# shemLampsV2.net
KiCad netlist of a schematic drawn in EAGLE
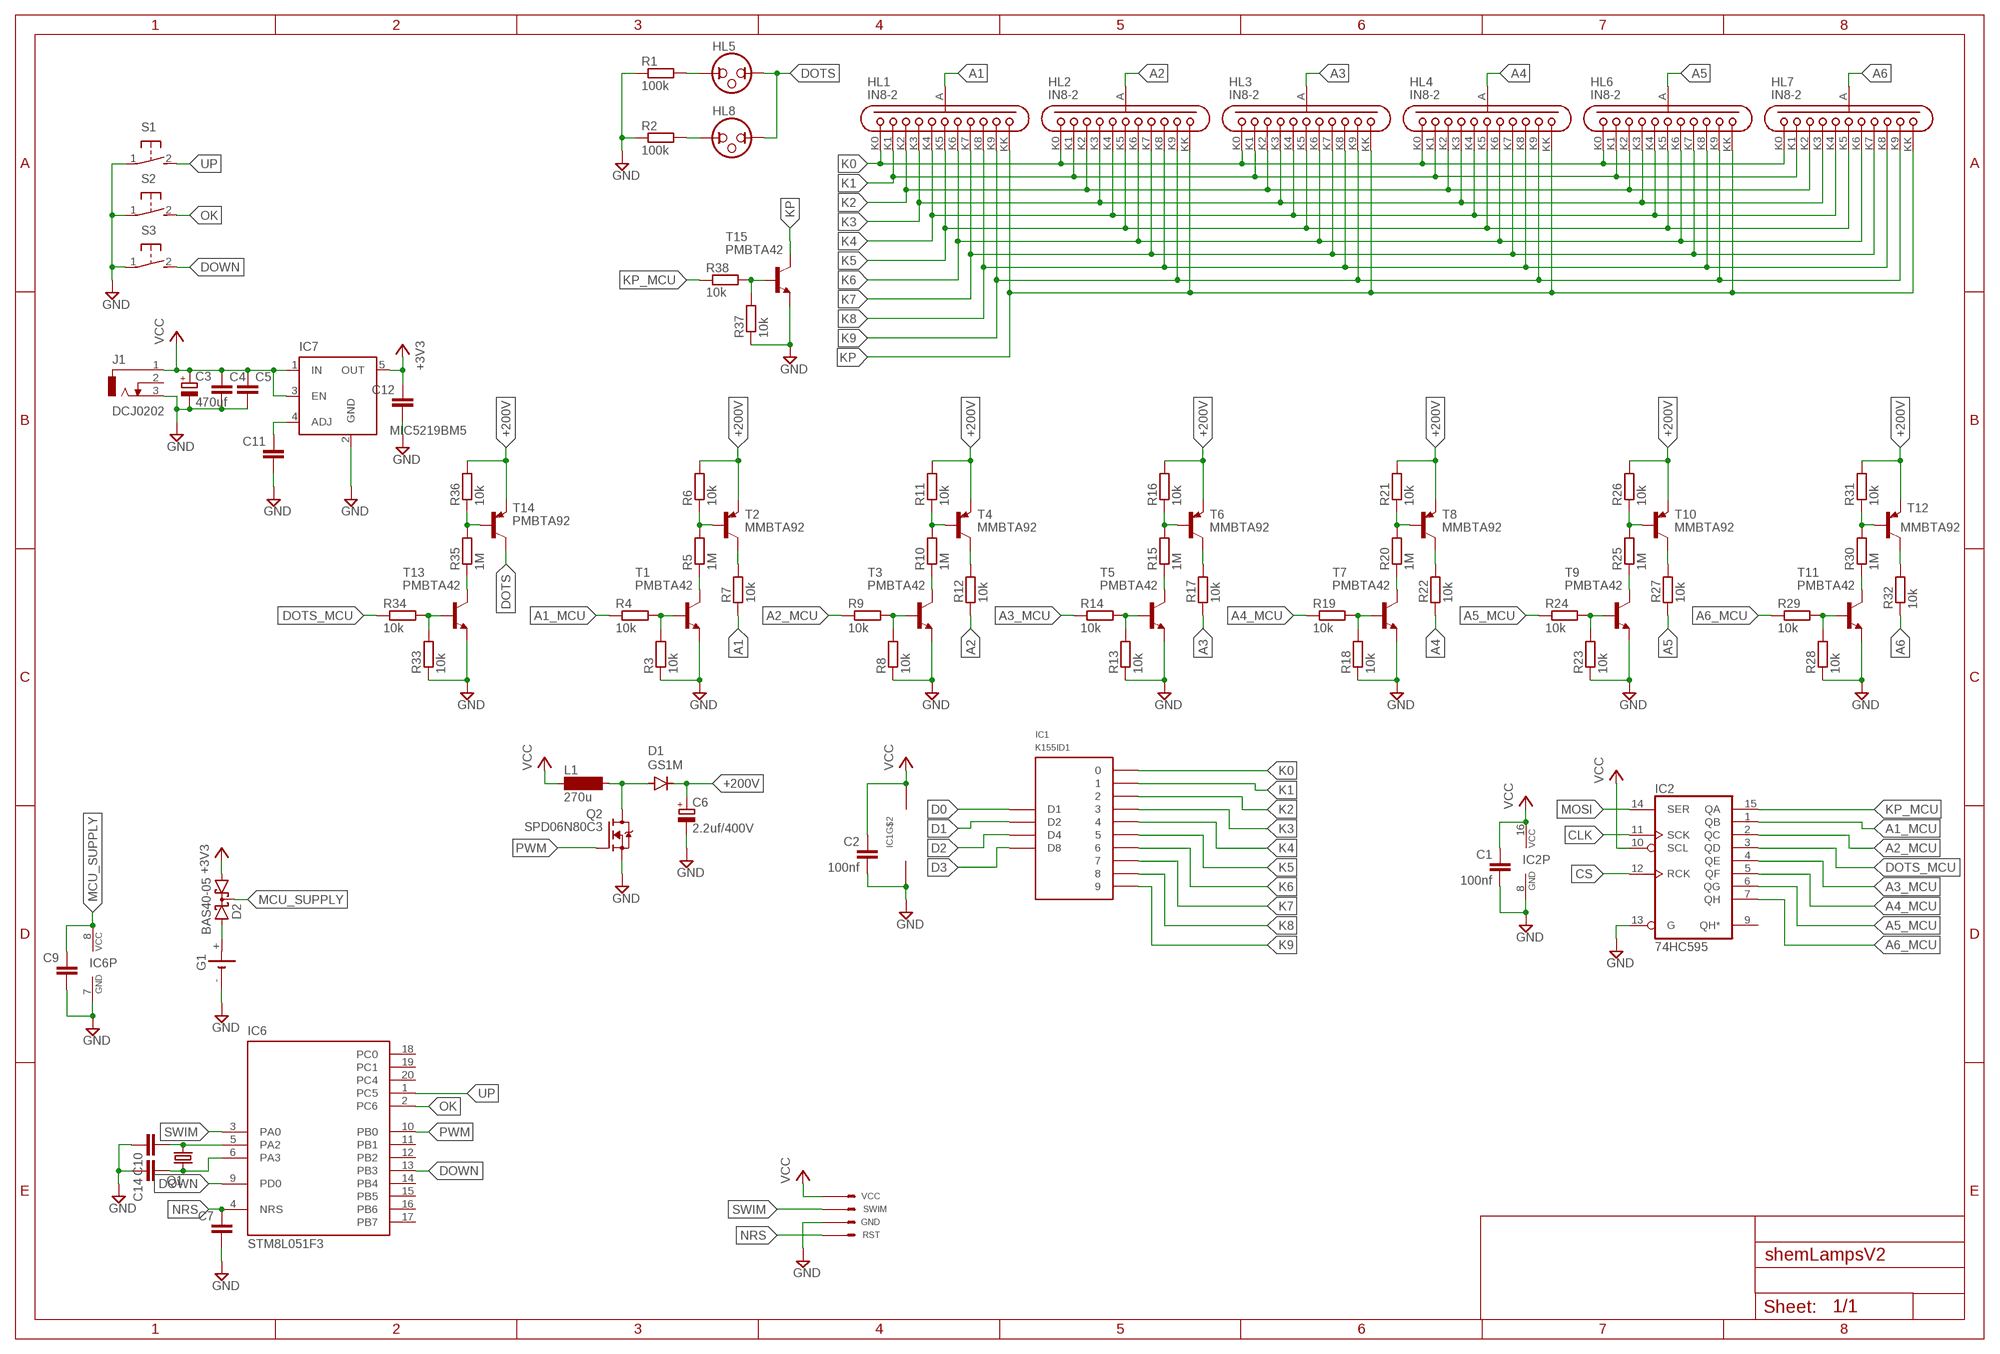
[diagram p0: schematic, sheet 1]

(export (version "E")
  (design (tool "Eeschema 10.0.6"))
  (components
    (comp (ref "C1")
      (value "100nf")
      (footprint "eagle-import:C0805")
      (libsource (lib "eagle-import") (part "CAP"))
    )
    (comp (ref "C2")
      (value "100nf")
      (footprint "eagle-import:C0805")
      (libsource (lib "eagle-import") (part "CAP"))
    )
    (comp (ref "C3")
      (value "470uf")
      (footprint "eagle-import:E3,5-8")
      (libsource (lib "eagle-import") (part "CPOL-EUE3.5-8"))
    )
    (comp (ref "C4")
      (value "C0805")
      (footprint "eagle-import:CAPC2113X70")
      (libsource (lib "eagle-import") (part "C0805"))
    )
    (comp (ref "C5")
      (value "C0805")
      (footprint "eagle-import:CAPC2113X70")
      (libsource (lib "eagle-import") (part "C0805"))
    )
    (comp (ref "C6")
      (value "2.2uf/400V")
      (footprint "eagle-import:E3,5-8")
      (libsource (lib "eagle-import") (part "CPOL-EUE3.5-8"))
    )
    (comp (ref "C7")
      (value "C0805")
      (footprint "eagle-import:CAPC2113X70")
      (libsource (lib "eagle-import") (part "C0805"))
    )
    (comp (ref "C9")
      (value "C0805")
      (footprint "eagle-import:CAPC2113X70")
      (libsource (lib "eagle-import") (part "C0805"))
    )
    (comp (ref "C10")
      (value "C0805")
      (footprint "eagle-import:CAPC2113X70")
      (libsource (lib "eagle-import") (part "C0805"))
    )
    (comp (ref "C11")
      (value "C0805")
      (footprint "eagle-import:CAPC2113X70")
      (libsource (lib "eagle-import") (part "C0805"))
    )
    (comp (ref "C12")
      (value "C0805")
      (footprint "eagle-import:CAPC2113X70")
      (libsource (lib "eagle-import") (part "C0805"))
    )
    (comp (ref "C14")
      (value "C0805")
      (footprint "eagle-import:CAPC2113X70")
      (libsource (lib "eagle-import") (part "C0805"))
    )
    (comp (ref "D1")
      (value "GS1M")
      (footprint "eagle-import:DO-214AC")
      (libsource (lib "eagle-import") (part "DIODE-DO-214AC"))
    )
    (comp (ref "D2")
      (value "BAS40-05")
      (footprint "eagle-import:SOT23")
      (libsource (lib "eagle-import") (part "BAS40-05"))
    )
    (comp (ref "G1")
      (value "BATTERY")
      (footprint "eagle-import:CH291-1220LF_W")
      (libsource (lib "eagle-import") (part "BATTERY"))
    )
    (comp (ref "HL1")
      (value "IN8-2")
      (footprint "eagle-import:IN8-2")
      (libsource (lib "eagle-import") (part "IN8-2"))
    )
    (comp (ref "HL2")
      (value "IN8-2")
      (footprint "eagle-import:IN8-2")
      (libsource (lib "eagle-import") (part "IN8-2"))
    )
    (comp (ref "HL3")
      (value "IN8-2")
      (footprint "eagle-import:IN8-2")
      (libsource (lib "eagle-import") (part "IN8-2"))
    )
    (comp (ref "HL4")
      (value "IN8-2")
      (footprint "eagle-import:IN8-2")
      (libsource (lib "eagle-import") (part "IN8-2"))
    )
    (comp (ref "HL5")
      (value "NEON_LAMP")
      (footprint "eagle-import:NEON_LAMP")
      (libsource (lib "eagle-import") (part "NEON_LAMP"))
    )
    (comp (ref "HL6")
      (value "IN8-2")
      (footprint "eagle-import:IN8-2")
      (libsource (lib "eagle-import") (part "IN8-2"))
    )
    (comp (ref "HL7")
      (value "IN8-2")
      (footprint "eagle-import:IN8-2")
      (libsource (lib "eagle-import") (part "IN8-2"))
    )
    (comp (ref "HL8")
      (value "NEON_LAMP")
      (footprint "eagle-import:NEON_LAMP")
      (libsource (lib "eagle-import") (part "NEON_LAMP"))
    )
    (comp (ref "IC1")
      (value "K155ID1")
      (footprint "eagle-import:DIL16")
      (libsource (lib "eagle-import") (part "K155ID1"))
    )
    (comp (ref "IC2")
      (value "74HC595")
      (footprint "eagle-import:TSSOP16L")
      (libsource (lib "eagle-import") (part "74HC595"))
    )
    (comp (ref "IC6")
      (value "STM8L051F3")
      (footprint "eagle-import:TSSOP-20")
      (libsource (lib "eagle-import") (part "STM8L051F3"))
    )
    (comp (ref "IC7")
      (value "MIC5219BM5")
      (footprint "eagle-import:SOT23-5")
      (fields (field (name "MF") "ALTERA CORPORATION") (field (name "MPN") "MIC5219BM5 TR"))
      (libsource (lib "eagle-import") (part "MIC5219BM5"))
    )
    (comp (ref "J1")
      (value "DCJ0202")
      (footprint "eagle-import:DCJ0202")
      (libsource (lib "eagle-import") (part "DCJ0202"))
    )
    (comp (ref "L1")
      (value "270u")
      (footprint "eagle-import:BS11")
      (libsource (lib "eagle-import") (part "BS11"))
    )
    (comp (ref "Q1")
      (value "FC-12M")
      (footprint "eagle-import:FC-12M")
      (libsource (lib "eagle-import") (part "FC-12M"))
    )
    (comp (ref "Q2")
      (value "SPD06N80C3")
      (footprint "eagle-import:TO252")
      (libsource (lib "eagle-import") (part "SPD06N80C3"))
    )
    (comp (ref "R1")
      (value "100k")
      (footprint "eagle-import:0207_10")
      (libsource (lib "eagle-import") (part "R-EU_0207/10"))
    )
    (comp (ref "R2")
      (value "100k")
      (footprint "eagle-import:0207_10")
      (libsource (lib "eagle-import") (part "R-EU_0207/10"))
    )
    (comp (ref "R3")
      (value "10k")
      (footprint "eagle-import:R0805")
      (libsource (lib "eagle-import") (part "RES"))
    )
    (comp (ref "R4")
      (value "10k")
      (footprint "eagle-import:R0805")
      (libsource (lib "eagle-import") (part "RES"))
    )
    (comp (ref "R5")
      (value "1M")
      (footprint "eagle-import:R0805")
      (libsource (lib "eagle-import") (part "RES"))
    )
    (comp (ref "R6")
      (value "10k")
      (footprint "eagle-import:R0805")
      (libsource (lib "eagle-import") (part "RES"))
    )
    (comp (ref "R7")
      (value "10k")
      (footprint "eagle-import:R0805")
      (libsource (lib "eagle-import") (part "RES"))
    )
    (comp (ref "R8")
      (value "10k")
      (footprint "eagle-import:R0805")
      (libsource (lib "eagle-import") (part "RES"))
    )
    (comp (ref "R9")
      (value "10k")
      (footprint "eagle-import:R0805")
      (libsource (lib "eagle-import") (part "RES"))
    )
    (comp (ref "R10")
      (value "1M")
      (footprint "eagle-import:R0805")
      (libsource (lib "eagle-import") (part "RES"))
    )
    (comp (ref "R11")
      (value "10k")
      (footprint "eagle-import:R0805")
      (libsource (lib "eagle-import") (part "RES"))
    )
    (comp (ref "R12")
      (value "10k")
      (footprint "eagle-import:R0805")
      (libsource (lib "eagle-import") (part "RES"))
    )
    (comp (ref "R13")
      (value "10k")
      (footprint "eagle-import:R0805")
      (libsource (lib "eagle-import") (part "RES"))
    )
    (comp (ref "R14")
      (value "10k")
      (footprint "eagle-import:R0805")
      (libsource (lib "eagle-import") (part "RES"))
    )
    (comp (ref "R15")
      (value "1M")
      (footprint "eagle-import:R0805")
      (libsource (lib "eagle-import") (part "RES"))
    )
    (comp (ref "R16")
      (value "10k")
      (footprint "eagle-import:R0805")
      (libsource (lib "eagle-import") (part "RES"))
    )
    (comp (ref "R17")
      (value "10k")
      (footprint "eagle-import:R0805")
      (libsource (lib "eagle-import") (part "RES"))
    )
    (comp (ref "R18")
      (value "10k")
      (footprint "eagle-import:R0805")
      (libsource (lib "eagle-import") (part "RES"))
    )
    (comp (ref "R19")
      (value "10k")
      (footprint "eagle-import:R0805")
      (libsource (lib "eagle-import") (part "RES"))
    )
    (comp (ref "R20")
      (value "1M")
      (footprint "eagle-import:R0805")
      (libsource (lib "eagle-import") (part "RES"))
    )
    (comp (ref "R21")
      (value "10k")
      (footprint "eagle-import:R0805")
      (libsource (lib "eagle-import") (part "RES"))
    )
    (comp (ref "R22")
      (value "10k")
      (footprint "eagle-import:R0805")
      (libsource (lib "eagle-import") (part "RES"))
    )
    (comp (ref "R23")
      (value "10k")
      (footprint "eagle-import:R0805")
      (libsource (lib "eagle-import") (part "RES"))
    )
    (comp (ref "R24")
      (value "10k")
      (footprint "eagle-import:R0805")
      (libsource (lib "eagle-import") (part "RES"))
    )
    (comp (ref "R25")
      (value "1M")
      (footprint "eagle-import:R0805")
      (libsource (lib "eagle-import") (part "RES"))
    )
    (comp (ref "R26")
      (value "10k")
      (footprint "eagle-import:R0805")
      (libsource (lib "eagle-import") (part "RES"))
    )
    (comp (ref "R27")
      (value "10k")
      (footprint "eagle-import:R0805")
      (libsource (lib "eagle-import") (part "RES"))
    )
    (comp (ref "R28")
      (value "10k")
      (footprint "eagle-import:R0805")
      (libsource (lib "eagle-import") (part "RES"))
    )
    (comp (ref "R29")
      (value "10k")
      (footprint "eagle-import:R0805")
      (libsource (lib "eagle-import") (part "RES"))
    )
    (comp (ref "R30")
      (value "1M")
      (footprint "eagle-import:R0805")
      (libsource (lib "eagle-import") (part "RES"))
    )
    (comp (ref "R31")
      (value "10k")
      (footprint "eagle-import:R0805")
      (libsource (lib "eagle-import") (part "RES"))
    )
    (comp (ref "R32")
      (value "10k")
      (footprint "eagle-import:R0805")
      (libsource (lib "eagle-import") (part "RES"))
    )
    (comp (ref "R33")
      (value "10k")
      (footprint "eagle-import:R0805")
      (libsource (lib "eagle-import") (part "RES"))
    )
    (comp (ref "R34")
      (value "10k")
      (footprint "eagle-import:R0805")
      (libsource (lib "eagle-import") (part "RES"))
    )
    (comp (ref "R35")
      (value "1M")
      (footprint "eagle-import:R0805")
      (libsource (lib "eagle-import") (part "RES"))
    )
    (comp (ref "R36")
      (value "10k")
      (footprint "eagle-import:R0805")
      (libsource (lib "eagle-import") (part "RES"))
    )
    (comp (ref "R37")
      (value "10k")
      (footprint "eagle-import:R0805")
      (libsource (lib "eagle-import") (part "RES"))
    )
    (comp (ref "R38")
      (value "10k")
      (footprint "eagle-import:R0805")
      (libsource (lib "eagle-import") (part "RES"))
    )
    (comp (ref "S1")
      (value "31-XX")
      (footprint "eagle-import:B3F-31XX")
      (fields (field (name "MPN") "B3F-3100"))
      (libsource (lib "eagle-import") (part "31-XX"))
    )
    (comp (ref "S2")
      (value "31-XX")
      (footprint "eagle-import:B3F-31XX")
      (fields (field (name "MPN") "B3F-3100"))
      (libsource (lib "eagle-import") (part "31-XX"))
    )
    (comp (ref "S3")
      (value "31-XX")
      (footprint "eagle-import:B3F-31XX")
      (fields (field (name "MPN") "B3F-3100"))
      (libsource (lib "eagle-import") (part "31-XX"))
    )
    (comp (ref "SV1")
      (value "SWIM")
      (footprint "eagle-import:SWIM")
      (libsource (lib "eagle-import") (part "SWIM"))
    )
    (comp (ref "T1")
      (value "PMBTA42")
      (footprint "eagle-import:SOT23-BEC")
      (libsource (lib "eagle-import") (part "-NPN-SOT23-BECBC817-16"))
    )
    (comp (ref "T2")
      (value "MMBTA92")
      (footprint "eagle-import:SOT23-BEC")
      (libsource (lib "eagle-import") (part "-PNP-SOT23-BECBC807-16"))
    )
    (comp (ref "T3")
      (value "PMBTA42")
      (footprint "eagle-import:SOT23-BEC")
      (libsource (lib "eagle-import") (part "-NPN-SOT23-BECBC817-16"))
    )
    (comp (ref "T4")
      (value "MMBTA92")
      (footprint "eagle-import:SOT23-BEC")
      (libsource (lib "eagle-import") (part "-PNP-SOT23-BECBC807-16"))
    )
    (comp (ref "T5")
      (value "PMBTA42")
      (footprint "eagle-import:SOT23-BEC")
      (libsource (lib "eagle-import") (part "-NPN-SOT23-BECBC817-16"))
    )
    (comp (ref "T6")
      (value "MMBTA92")
      (footprint "eagle-import:SOT23-BEC")
      (libsource (lib "eagle-import") (part "-PNP-SOT23-BECBC807-16"))
    )
    (comp (ref "T7")
      (value "PMBTA42")
      (footprint "eagle-import:SOT23-BEC")
      (libsource (lib "eagle-import") (part "-NPN-SOT23-BECBC817-16"))
    )
    (comp (ref "T8")
      (value "MMBTA92")
      (footprint "eagle-import:SOT23-BEC")
      (libsource (lib "eagle-import") (part "-PNP-SOT23-BECBC807-16"))
    )
    (comp (ref "T9")
      (value "PMBTA42")
      (footprint "eagle-import:SOT23-BEC")
      (libsource (lib "eagle-import") (part "-NPN-SOT23-BECBC817-16"))
    )
    (comp (ref "T10")
      (value "MMBTA92")
      (footprint "eagle-import:SOT23-BEC")
      (libsource (lib "eagle-import") (part "-PNP-SOT23-BECBC807-16"))
    )
    (comp (ref "T11")
      (value "PMBTA42")
      (footprint "eagle-import:SOT23-BEC")
      (libsource (lib "eagle-import") (part "-NPN-SOT23-BECBC817-16"))
    )
    (comp (ref "T12")
      (value "MMBTA92")
      (footprint "eagle-import:SOT23-BEC")
      (libsource (lib "eagle-import") (part "-PNP-SOT23-BECBC807-16"))
    )
    (comp (ref "T13")
      (value "PMBTA42")
      (footprint "eagle-import:SOT23-BEC")
      (libsource (lib "eagle-import") (part "-NPN-SOT23-BECBC817-16"))
    )
    (comp (ref "T14")
      (value "PMBTA92")
      (footprint "eagle-import:SOT23-BEC")
      (libsource (lib "eagle-import") (part "-PNP-SOT23-BECBC807-16"))
    )
    (comp (ref "T15")
      (value "PMBTA42")
      (footprint "eagle-import:SOT23-BEC")
      (libsource (lib "eagle-import") (part "-NPN-SOT23-BECBC817-16"))
    )
  )
  (nets
    (net (code "1") (name "+3V3") (class "Default")
      (node (ref "C12") (pin "1") (pinfunction "1_1") (pintype "passive"))
      (node (ref "D2") (pin "1") (pinfunction "A1_1") (pintype "passive"))
      (node (ref "IC7") (pin "5") (pinfunction "OUT_5") (pintype "output"))
    )
    (net (code "2") (name "+200V") (class "Default")
      (node (ref "C6") (pin "+") (pinfunction "+_+") (pintype "passive"))
      (node (ref "D1") (pin "C") (pinfunction "C_C") (pintype "passive"))
      (node (ref "R11") (pin "2") (pinfunction "2_2") (pintype "passive"))
      (node (ref "R16") (pin "2") (pinfunction "2_2") (pintype "passive"))
      (node (ref "R21") (pin "2") (pinfunction "2_2") (pintype "passive"))
      (node (ref "R26") (pin "2") (pinfunction "2_2") (pintype "passive"))
      (node (ref "R31") (pin "2") (pinfunction "2_2") (pintype "passive"))
      (node (ref "R36") (pin "2") (pinfunction "2_2") (pintype "passive"))
      (node (ref "R6") (pin "2") (pinfunction "2_2") (pintype "passive"))
      (node (ref "T10") (pin "E") (pinfunction "E_E") (pintype "passive"))
      (node (ref "T12") (pin "E") (pinfunction "E_E") (pintype "passive"))
      (node (ref "T14") (pin "E") (pinfunction "E_E") (pintype "passive"))
      (node (ref "T2") (pin "E") (pinfunction "E_E") (pintype "passive"))
      (node (ref "T4") (pin "E") (pinfunction "E_E") (pintype "passive"))
      (node (ref "T6") (pin "E") (pinfunction "E_E") (pintype "passive"))
      (node (ref "T8") (pin "E") (pinfunction "E_E") (pintype "passive"))
    )
    (net (code "3") (name "A1") (class "Default")
      (node (ref "HL1") (pin "A") (pinfunction "A_A") (pintype "passive"))
      (node (ref "R7") (pin "1") (pinfunction "1_1") (pintype "passive"))
    )
    (net (code "4") (name "A1_MCU") (class "Default")
      (node (ref "IC2") (pin "1") (pinfunction "QB_1") (pintype "tri_state"))
      (node (ref "R4") (pin "1") (pinfunction "1_1") (pintype "passive"))
    )
    (net (code "5") (name "A2") (class "Default")
      (node (ref "HL2") (pin "A") (pinfunction "A_A") (pintype "passive"))
      (node (ref "R12") (pin "1") (pinfunction "1_1") (pintype "passive"))
    )
    (net (code "6") (name "A2_MCU") (class "Default")
      (node (ref "IC2") (pin "2") (pinfunction "QC_2") (pintype "tri_state"))
      (node (ref "R9") (pin "1") (pinfunction "1_1") (pintype "passive"))
    )
    (net (code "7") (name "A3") (class "Default")
      (node (ref "HL3") (pin "A") (pinfunction "A_A") (pintype "passive"))
      (node (ref "R17") (pin "1") (pinfunction "1_1") (pintype "passive"))
    )
    (net (code "8") (name "A3_MCU") (class "Default")
      (node (ref "IC2") (pin "4") (pinfunction "QE_4") (pintype "tri_state"))
      (node (ref "R14") (pin "1") (pinfunction "1_1") (pintype "passive"))
    )
    (net (code "9") (name "A4") (class "Default")
      (node (ref "HL4") (pin "A") (pinfunction "A_A") (pintype "passive"))
      (node (ref "R22") (pin "1") (pinfunction "1_1") (pintype "passive"))
    )
    (net (code "10") (name "A4_MCU") (class "Default")
      (node (ref "IC2") (pin "5") (pinfunction "QF_5") (pintype "tri_state"))
      (node (ref "R19") (pin "1") (pinfunction "1_1") (pintype "passive"))
    )
    (net (code "11") (name "A5") (class "Default")
      (node (ref "HL6") (pin "A") (pinfunction "A_A") (pintype "passive"))
      (node (ref "R27") (pin "1") (pinfunction "1_1") (pintype "passive"))
    )
    (net (code "12") (name "A5_MCU") (class "Default")
      (node (ref "IC2") (pin "6") (pinfunction "QG_6") (pintype "tri_state"))
      (node (ref "R24") (pin "1") (pinfunction "1_1") (pintype "passive"))
    )
    (net (code "13") (name "A6") (class "Default")
      (node (ref "HL7") (pin "A") (pinfunction "A_A") (pintype "passive"))
      (node (ref "R32") (pin "1") (pinfunction "1_1") (pintype "passive"))
    )
    (net (code "14") (name "A6_MCU") (class "Default")
      (node (ref "IC2") (pin "7") (pinfunction "QH_7") (pintype "tri_state"))
      (node (ref "R29") (pin "1") (pinfunction "1_1") (pintype "passive"))
    )
    (net (code "15") (name "CLK") (class "Default")
      (node (ref "IC2") (pin "11") (pinfunction "SCK_11") (pintype "input"))
    )
    (net (code "16") (name "CS") (class "Default")
      (node (ref "IC2") (pin "12") (pinfunction "RCK_12") (pintype "input"))
    )
    (net (code "17") (name "D0") (class "Default")
      (node (ref "IC1") (pin "3") (pinfunction "D1_3") (pintype "input"))
    )
    (net (code "18") (name "D1") (class "Default")
      (node (ref "IC1") (pin "6") (pinfunction "D2_6") (pintype "input"))
    )
    (net (code "19") (name "D2") (class "Default")
      (node (ref "IC1") (pin "7") (pinfunction "D4_7") (pintype "input"))
    )
    (net (code "20") (name "D3") (class "Default")
      (node (ref "IC1") (pin "4") (pinfunction "D8_4") (pintype "input"))
    )
    (net (code "21") (name "DOTS") (class "Default")
      (node (ref "HL5") (pin "2") (pinfunction "2_2") (pintype "passive"))
      (node (ref "HL8") (pin "2") (pinfunction "2_2") (pintype "passive"))
      (node (ref "T14") (pin "C") (pinfunction "C_C") (pintype "passive"))
    )
    (net (code "22") (name "DOTS_MCU") (class "Default")
      (node (ref "IC2") (pin "3") (pinfunction "QD_3") (pintype "tri_state"))
      (node (ref "R34") (pin "1") (pinfunction "1_1") (pintype "passive"))
    )
    (net (code "23") (name "DOWN") (class "Default")
      (node (ref "IC6") (pin "13") (pinfunction "PB3_13") (pintype "bidirectional"))
      (node (ref "IC6") (pin "9") (pinfunction "PD0_9") (pintype "bidirectional"))
      (node (ref "S3") (pin "2") (pinfunction "S_2") (pintype "passive"))
    )
    (net (code "24") (name "GND") (class "Default")
      (node (ref "C1") (pin "2") (pinfunction "2_2") (pintype "passive"))
      (node (ref "C10") (pin "1") (pinfunction "1_1") (pintype "passive"))
      (node (ref "C11") (pin "2") (pinfunction "2_2") (pintype "passive"))
      (node (ref "C12") (pin "2") (pinfunction "2_2") (pintype "passive"))
      (node (ref "C14") (pin "1") (pinfunction "1_1") (pintype "passive"))
      (node (ref "C2") (pin "2") (pinfunction "2_2") (pintype "passive"))
      (node (ref "C3") (pin "-") (pinfunction "-_-") (pintype "passive"))
      (node (ref "C4") (pin "2") (pinfunction "2_2") (pintype "passive"))
      (node (ref "C5") (pin "2") (pinfunction "2_2") (pintype "passive"))
      (node (ref "C6") (pin "-") (pinfunction "-_-") (pintype "passive"))
      (node (ref "C7") (pin "2") (pinfunction "2_2") (pintype "passive"))
      (node (ref "C9") (pin "2") (pinfunction "2_2") (pintype "passive"))
      (node (ref "G1") (pin "-") (pinfunction "-_-") (pintype "passive"))
      (node (ref "IC1") (pin "12") (pinfunction "GND_12") (pintype "power_in"))
      (node (ref "IC2") (pin "13") (pinfunction "G_13") (pintype "input"))
      (node (ref "IC2") (pin "8") (pinfunction "GND_8") (pintype "power_in"))
      (node (ref "IC6") (pin "7") (pinfunction "GND_7") (pintype "power_in"))
      (node (ref "IC7") (pin "2") (pinfunction "GND_2") (pintype "power_in"))
      (node (ref "J1") (pin "3") (pinfunction "3_3") (pintype "passive"))
      (node (ref "Q2") (pin "2") (pinfunction "S_2") (pintype "passive"))
      (node (ref "R1") (pin "1") (pinfunction "1_1") (pintype "passive"))
      (node (ref "R13") (pin "1") (pinfunction "1_1") (pintype "passive"))
      (node (ref "R18") (pin "1") (pinfunction "1_1") (pintype "passive"))
      (node (ref "R2") (pin "1") (pinfunction "1_1") (pintype "passive"))
      (node (ref "R23") (pin "1") (pinfunction "1_1") (pintype "passive"))
      (node (ref "R28") (pin "1") (pinfunction "1_1") (pintype "passive"))
      (node (ref "R3") (pin "1") (pinfunction "1_1") (pintype "passive"))
      (node (ref "R33") (pin "1") (pinfunction "1_1") (pintype "passive"))
      (node (ref "R37") (pin "1") (pinfunction "1_1") (pintype "passive"))
      (node (ref "R8") (pin "1") (pinfunction "1_1") (pintype "passive"))
      (node (ref "S1") (pin "1") (pinfunction "P_1") (pintype "passive"))
      (node (ref "S2") (pin "1") (pinfunction "P_1") (pintype "passive"))
      (node (ref "S3") (pin "1") (pinfunction "P_1") (pintype "passive"))
      (node (ref "SV1") (pin "GND") (pinfunction "GND_GND") (pintype "power_in"))
      (node (ref "T1") (pin "E") (pinfunction "E_E") (pintype "passive"))
      (node (ref "T11") (pin "E") (pinfunction "E_E") (pintype "passive"))
      (node (ref "T13") (pin "E") (pinfunction "E_E") (pintype "passive"))
      (node (ref "T15") (pin "E") (pinfunction "E_E") (pintype "passive"))
      (node (ref "T3") (pin "E") (pinfunction "E_E") (pintype "passive"))
      (node (ref "T5") (pin "E") (pinfunction "E_E") (pintype "passive"))
      (node (ref "T7") (pin "E") (pinfunction "E_E") (pintype "passive"))
      (node (ref "T9") (pin "E") (pinfunction "E_E") (pintype "passive"))
    )
    (net (code "25") (name "K0") (class "Default")
      (node (ref "HL1") (pin "K0") (pinfunction "K0_K0") (pintype "passive"))
      (node (ref "HL2") (pin "K0") (pinfunction "K0_K0") (pintype "passive"))
      (node (ref "HL3") (pin "K0") (pinfunction "K0_K0") (pintype "passive"))
      (node (ref "HL4") (pin "K0") (pinfunction "K0_K0") (pintype "passive"))
      (node (ref "HL6") (pin "K0") (pinfunction "K0_K0") (pintype "passive"))
      (node (ref "HL7") (pin "K0") (pinfunction "K0_K0") (pintype "passive"))
      (node (ref "IC1") (pin "16") (pinfunction "0_16") (pintype "output"))
    )
    (net (code "26") (name "K1") (class "Default")
      (node (ref "HL1") (pin "K1") (pinfunction "K1_K1") (pintype "passive"))
      (node (ref "HL2") (pin "K1") (pinfunction "K1_K1") (pintype "passive"))
      (node (ref "HL3") (pin "K1") (pinfunction "K1_K1") (pintype "passive"))
      (node (ref "HL4") (pin "K1") (pinfunction "K1_K1") (pintype "passive"))
      (node (ref "HL6") (pin "K1") (pinfunction "K1_K1") (pintype "passive"))
      (node (ref "HL7") (pin "K1") (pinfunction "K1_K1") (pintype "passive"))
      (node (ref "IC1") (pin "15") (pinfunction "1_15") (pintype "output"))
    )
    (net (code "27") (name "K2") (class "Default")
      (node (ref "HL1") (pin "K2") (pinfunction "K2_K2") (pintype "passive"))
      (node (ref "HL2") (pin "K2") (pinfunction "K2_K2") (pintype "passive"))
      (node (ref "HL3") (pin "K2") (pinfunction "K2_K2") (pintype "passive"))
      (node (ref "HL4") (pin "K2") (pinfunction "K2_K2") (pintype "passive"))
      (node (ref "HL6") (pin "K2") (pinfunction "K2_K2") (pintype "passive"))
      (node (ref "HL7") (pin "K2") (pinfunction "K2_K2") (pintype "passive"))
      (node (ref "IC1") (pin "8") (pinfunction "2_8") (pintype "output"))
    )
    (net (code "28") (name "K3") (class "Default")
      (node (ref "HL1") (pin "K3") (pinfunction "K3_K3") (pintype "passive"))
      (node (ref "HL2") (pin "K3") (pinfunction "K3_K3") (pintype "passive"))
      (node (ref "HL3") (pin "K3") (pinfunction "K3_K3") (pintype "passive"))
      (node (ref "HL4") (pin "K3") (pinfunction "K3_K3") (pintype "passive"))
      (node (ref "HL6") (pin "K3") (pinfunction "K3_K3") (pintype "passive"))
      (node (ref "HL7") (pin "K3") (pinfunction "K3_K3") (pintype "passive"))
      (node (ref "IC1") (pin "9") (pinfunction "3_9") (pintype "output"))
    )
    (net (code "29") (name "K4") (class "Default")
      (node (ref "HL1") (pin "K4") (pinfunction "K4_K4") (pintype "passive"))
      (node (ref "HL2") (pin "K4") (pinfunction "K4_K4") (pintype "passive"))
      (node (ref "HL3") (pin "K4") (pinfunction "K4_K4") (pintype "passive"))
      (node (ref "HL4") (pin "K4") (pinfunction "K4_K4") (pintype "passive"))
      (node (ref "HL6") (pin "K4") (pinfunction "K4_K4") (pintype "passive"))
      (node (ref "HL7") (pin "K4") (pinfunction "K4_K4") (pintype "passive"))
      (node (ref "IC1") (pin "13") (pinfunction "4_13") (pintype "output"))
    )
    (net (code "30") (name "K5") (class "Default")
      (node (ref "HL1") (pin "K5") (pinfunction "K5_K5") (pintype "passive"))
      (node (ref "HL2") (pin "K5") (pinfunction "K5_K5") (pintype "passive"))
      (node (ref "HL3") (pin "K5") (pinfunction "K5_K5") (pintype "passive"))
      (node (ref "HL4") (pin "K5") (pinfunction "K5_K5") (pintype "passive"))
      (node (ref "HL6") (pin "K5") (pinfunction "K5_K5") (pintype "passive"))
      (node (ref "HL7") (pin "K5") (pinfunction "K5_K5") (pintype "passive"))
      (node (ref "IC1") (pin "14") (pinfunction "5_14") (pintype "output"))
    )
    (net (code "31") (name "K6") (class "Default")
      (node (ref "HL1") (pin "K6") (pinfunction "K6_K6") (pintype "passive"))
      (node (ref "HL2") (pin "K6") (pinfunction "K6_K6") (pintype "passive"))
      (node (ref "HL3") (pin "K6") (pinfunction "K6_K6") (pintype "passive"))
      (node (ref "HL4") (pin "K6") (pinfunction "K6_K6") (pintype "passive"))
      (node (ref "HL6") (pin "K6") (pinfunction "K6_K6") (pintype "passive"))
      (node (ref "HL7") (pin "K6") (pinfunction "K6_K6") (pintype "passive"))
      (node (ref "IC1") (pin "11") (pinfunction "6_11") (pintype "output"))
    )
    (net (code "32") (name "K7") (class "Default")
      (node (ref "HL1") (pin "K7") (pinfunction "K7_K7") (pintype "passive"))
      (node (ref "HL2") (pin "K7") (pinfunction "K7_K7") (pintype "passive"))
      (node (ref "HL3") (pin "K7") (pinfunction "K7_K7") (pintype "passive"))
      (node (ref "HL4") (pin "K7") (pinfunction "K7_K7") (pintype "passive"))
      (node (ref "HL6") (pin "K7") (pinfunction "K7_K7") (pintype "passive"))
      (node (ref "HL7") (pin "K7") (pinfunction "K7_K7") (pintype "passive"))
      (node (ref "IC1") (pin "10") (pinfunction "7_10") (pintype "output"))
    )
    (net (code "33") (name "K8") (class "Default")
      (node (ref "HL1") (pin "K8") (pinfunction "K8_K8") (pintype "passive"))
      (node (ref "HL2") (pin "K8") (pinfunction "K8_K8") (pintype "passive"))
      (node (ref "HL3") (pin "K8") (pinfunction "K8_K8") (pintype "passive"))
      (node (ref "HL4") (pin "K8") (pinfunction "K8_K8") (pintype "passive"))
      (node (ref "HL6") (pin "K8") (pinfunction "K8_K8") (pintype "passive"))
      (node (ref "HL7") (pin "K8") (pinfunction "K8_K8") (pintype "passive"))
      (node (ref "IC1") (pin "1") (pinfunction "8_1") (pintype "output"))
    )
    (net (code "34") (name "K9") (class "Default")
      (node (ref "HL1") (pin "K9") (pinfunction "K9_K9") (pintype "passive"))
      (node (ref "HL2") (pin "K9") (pinfunction "K9_K9") (pintype "passive"))
      (node (ref "HL3") (pin "K9") (pinfunction "K9_K9") (pintype "passive"))
      (node (ref "HL4") (pin "K9") (pinfunction "K9_K9") (pintype "passive"))
      (node (ref "HL6") (pin "K9") (pinfunction "K9_K9") (pintype "passive"))
      (node (ref "HL7") (pin "K9") (pinfunction "K9_K9") (pintype "passive"))
      (node (ref "IC1") (pin "2") (pinfunction "9_2") (pintype "output"))
    )
    (net (code "35") (name "KP") (class "Default")
      (node (ref "HL1") (pin "KK") (pinfunction "KK_KK") (pintype "passive"))
      (node (ref "HL2") (pin "KK") (pinfunction "KK_KK") (pintype "passive"))
      (node (ref "HL3") (pin "KK") (pinfunction "KK_KK") (pintype "passive"))
      (node (ref "HL4") (pin "KK") (pinfunction "KK_KK") (pintype "passive"))
      (node (ref "HL6") (pin "KK") (pinfunction "KK_KK") (pintype "passive"))
      (node (ref "HL7") (pin "KK") (pinfunction "KK_KK") (pintype "passive"))
      (node (ref "T15") (pin "C") (pinfunction "C_C") (pintype "passive"))
    )
    (net (code "36") (name "KP_MCU") (class "Default")
      (node (ref "IC2") (pin "15") (pinfunction "QA_15") (pintype "tri_state"))
      (node (ref "R38") (pin "1") (pinfunction "1_1") (pintype "passive"))
    )
    (net (code "37") (name "MCU_SUPPLY") (class "Default")
      (node (ref "C9") (pin "1") (pinfunction "1_1") (pintype "passive"))
      (node (ref "D2") (pin "3") (pinfunction "C_3") (pintype "passive"))
      (node (ref "IC6") (pin "8") (pinfunction "VCC_8") (pintype "power_in"))
    )
    (net (code "38") (name "MOSI") (class "Default")
      (node (ref "IC2") (pin "14") (pinfunction "SER_14") (pintype "input"))
    )
    (net (code "39") (name "NRS") (class "Default")
      (node (ref "C7") (pin "1") (pinfunction "1_1") (pintype "passive"))
      (node (ref "IC6") (pin "4") (pinfunction "NRS_4") (pintype "bidirectional"))
      (node (ref "SV1") (pin "NRS") (pinfunction "RST_NRS") (pintype "bidirectional"))
    )
    (net (code "40") (name "Net-(D2-A2)") (class "Default")
      (node (ref "D2") (pin "2") (pinfunction "A2_2") (pintype "passive"))
      (node (ref "G1") (pin "+") (pinfunction "+_+") (pintype "passive"))
    )
    (net (code "41") (name "Net-(HL5-Pad1)") (class "Default")
      (node (ref "HL5") (pin "1") (pinfunction "1_1") (pintype "passive"))
      (node (ref "R1") (pin "2") (pinfunction "2_2") (pintype "passive"))
    )
    (net (code "42") (name "Net-(HL8-Pad1)") (class "Default")
      (node (ref "HL8") (pin "1") (pinfunction "1_1") (pintype "passive"))
      (node (ref "R2") (pin "2") (pinfunction "2_2") (pintype "passive"))
    )
    (net (code "43") (name "Net-(IC6A-PA2)") (class "Default")
      (node (ref "C10") (pin "2") (pinfunction "2_2") (pintype "passive"))
      (node (ref "IC6") (pin "5") (pinfunction "PA2_5") (pintype "bidirectional"))
      (node (ref "Q1") (pin "2") (pinfunction "2_2") (pintype "passive"))
    )
    (net (code "44") (name "Net-(IC6A-PA3)") (class "Default")
      (node (ref "C14") (pin "2") (pinfunction "2_2") (pintype "passive"))
      (node (ref "IC6") (pin "6") (pinfunction "PA3_6") (pintype "bidirectional"))
      (node (ref "Q1") (pin "1") (pinfunction "1_1") (pintype "passive"))
    )
    (net (code "45") (name "Net-(IC7-ADJ)") (class "Default")
      (node (ref "C11") (pin "1") (pinfunction "1_1") (pintype "passive"))
      (node (ref "IC7") (pin "4") (pinfunction "ADJ_4") (pintype "passive"))
    )
    (net (code "46") (name "Net-(Q2-D)") (class "Default")
      (node (ref "D1") (pin "A") (pinfunction "A_A") (pintype "passive"))
      (node (ref "L1") (pin "2") (pinfunction "2_2") (pintype "passive"))
      (node (ref "Q2") (pin "3") (pinfunction "D_3") (pintype "passive"))
    )
    (net (code "47") (name "Net-(R3-Pad2)") (class "Default")
      (node (ref "R3") (pin "2") (pinfunction "2_2") (pintype "passive"))
      (node (ref "R4") (pin "2") (pinfunction "2_2") (pintype "passive"))
      (node (ref "T1") (pin "B") (pinfunction "B_B") (pintype "passive"))
    )
    (net (code "48") (name "Net-(R5-Pad1)") (class "Default")
      (node (ref "R5") (pin "1") (pinfunction "1_1") (pintype "passive"))
      (node (ref "T1") (pin "C") (pinfunction "C_C") (pintype "passive"))
    )
    (net (code "49") (name "Net-(R5-Pad2)") (class "Default")
      (node (ref "R5") (pin "2") (pinfunction "2_2") (pintype "passive"))
      (node (ref "R6") (pin "1") (pinfunction "1_1") (pintype "passive"))
      (node (ref "T2") (pin "B") (pinfunction "B_B") (pintype "passive"))
    )
    (net (code "50") (name "Net-(R7-Pad2)") (class "Default")
      (node (ref "R7") (pin "2") (pinfunction "2_2") (pintype "passive"))
      (node (ref "T2") (pin "C") (pinfunction "C_C") (pintype "passive"))
    )
    (net (code "51") (name "Net-(R8-Pad2)") (class "Default")
      (node (ref "R8") (pin "2") (pinfunction "2_2") (pintype "passive"))
      (node (ref "R9") (pin "2") (pinfunction "2_2") (pintype "passive"))
      (node (ref "T3") (pin "B") (pinfunction "B_B") (pintype "passive"))
    )
    (net (code "52") (name "Net-(R10-Pad1)") (class "Default")
      (node (ref "R10") (pin "1") (pinfunction "1_1") (pintype "passive"))
      (node (ref "T3") (pin "C") (pinfunction "C_C") (pintype "passive"))
    )
    (net (code "53") (name "Net-(R10-Pad2)") (class "Default")
      (node (ref "R10") (pin "2") (pinfunction "2_2") (pintype "passive"))
      (node (ref "R11") (pin "1") (pinfunction "1_1") (pintype "passive"))
      (node (ref "T4") (pin "B") (pinfunction "B_B") (pintype "passive"))
    )
    (net (code "54") (name "Net-(R12-Pad2)") (class "Default")
      (node (ref "R12") (pin "2") (pinfunction "2_2") (pintype "passive"))
      (node (ref "T4") (pin "C") (pinfunction "C_C") (pintype "passive"))
    )
    (net (code "55") (name "Net-(R13-Pad2)") (class "Default")
      (node (ref "R13") (pin "2") (pinfunction "2_2") (pintype "passive"))
      (node (ref "R14") (pin "2") (pinfunction "2_2") (pintype "passive"))
      (node (ref "T5") (pin "B") (pinfunction "B_B") (pintype "passive"))
    )
    (net (code "56") (name "Net-(R15-Pad1)") (class "Default")
      (node (ref "R15") (pin "1") (pinfunction "1_1") (pintype "passive"))
      (node (ref "T5") (pin "C") (pinfunction "C_C") (pintype "passive"))
    )
    (net (code "57") (name "Net-(R15-Pad2)") (class "Default")
      (node (ref "R15") (pin "2") (pinfunction "2_2") (pintype "passive"))
      (node (ref "R16") (pin "1") (pinfunction "1_1") (pintype "passive"))
      (node (ref "T6") (pin "B") (pinfunction "B_B") (pintype "passive"))
    )
    (net (code "58") (name "Net-(R17-Pad2)") (class "Default")
      (node (ref "R17") (pin "2") (pinfunction "2_2") (pintype "passive"))
      (node (ref "T6") (pin "C") (pinfunction "C_C") (pintype "passive"))
    )
    (net (code "59") (name "Net-(R18-Pad2)") (class "Default")
      (node (ref "R18") (pin "2") (pinfunction "2_2") (pintype "passive"))
      (node (ref "R19") (pin "2") (pinfunction "2_2") (pintype "passive"))
      (node (ref "T7") (pin "B") (pinfunction "B_B") (pintype "passive"))
    )
    (net (code "60") (name "Net-(R20-Pad1)") (class "Default")
      (node (ref "R20") (pin "1") (pinfunction "1_1") (pintype "passive"))
      (node (ref "T7") (pin "C") (pinfunction "C_C") (pintype "passive"))
    )
    (net (code "61") (name "Net-(R20-Pad2)") (class "Default")
      (node (ref "R20") (pin "2") (pinfunction "2_2") (pintype "passive"))
      (node (ref "R21") (pin "1") (pinfunction "1_1") (pintype "passive"))
      (node (ref "T8") (pin "B") (pinfunction "B_B") (pintype "passive"))
    )
    (net (code "62") (name "Net-(R22-Pad2)") (class "Default")
      (node (ref "R22") (pin "2") (pinfunction "2_2") (pintype "passive"))
      (node (ref "T8") (pin "C") (pinfunction "C_C") (pintype "passive"))
    )
    (net (code "63") (name "Net-(R23-Pad2)") (class "Default")
      (node (ref "R23") (pin "2") (pinfunction "2_2") (pintype "passive"))
      (node (ref "R24") (pin "2") (pinfunction "2_2") (pintype "passive"))
      (node (ref "T9") (pin "B") (pinfunction "B_B") (pintype "passive"))
    )
    (net (code "64") (name "Net-(R25-Pad1)") (class "Default")
      (node (ref "R25") (pin "1") (pinfunction "1_1") (pintype "passive"))
      (node (ref "T9") (pin "C") (pinfunction "C_C") (pintype "passive"))
    )
    (net (code "65") (name "Net-(R25-Pad2)") (class "Default")
      (node (ref "R25") (pin "2") (pinfunction "2_2") (pintype "passive"))
      (node (ref "R26") (pin "1") (pinfunction "1_1") (pintype "passive"))
      (node (ref "T10") (pin "B") (pinfunction "B_B") (pintype "passive"))
    )
    (net (code "66") (name "Net-(R27-Pad2)") (class "Default")
      (node (ref "R27") (pin "2") (pinfunction "2_2") (pintype "passive"))
      (node (ref "T10") (pin "C") (pinfunction "C_C") (pintype "passive"))
    )
    (net (code "67") (name "Net-(R28-Pad2)") (class "Default")
      (node (ref "R28") (pin "2") (pinfunction "2_2") (pintype "passive"))
      (node (ref "R29") (pin "2") (pinfunction "2_2") (pintype "passive"))
      (node (ref "T11") (pin "B") (pinfunction "B_B") (pintype "passive"))
    )
    (net (code "68") (name "Net-(R30-Pad1)") (class "Default")
      (node (ref "R30") (pin "1") (pinfunction "1_1") (pintype "passive"))
      (node (ref "T11") (pin "C") (pinfunction "C_C") (pintype "passive"))
    )
    (net (code "69") (name "Net-(R30-Pad2)") (class "Default")
      (node (ref "R30") (pin "2") (pinfunction "2_2") (pintype "passive"))
      (node (ref "R31") (pin "1") (pinfunction "1_1") (pintype "passive"))
      (node (ref "T12") (pin "B") (pinfunction "B_B") (pintype "passive"))
    )
    (net (code "70") (name "Net-(R32-Pad2)") (class "Default")
      (node (ref "R32") (pin "2") (pinfunction "2_2") (pintype "passive"))
      (node (ref "T12") (pin "C") (pinfunction "C_C") (pintype "passive"))
    )
    (net (code "71") (name "Net-(R33-Pad2)") (class "Default")
      (node (ref "R33") (pin "2") (pinfunction "2_2") (pintype "passive"))
      (node (ref "R34") (pin "2") (pinfunction "2_2") (pintype "passive"))
      (node (ref "T13") (pin "B") (pinfunction "B_B") (pintype "passive"))
    )
    (net (code "72") (name "Net-(R35-Pad1)") (class "Default")
      (node (ref "R35") (pin "1") (pinfunction "1_1") (pintype "passive"))
      (node (ref "T13") (pin "C") (pinfunction "C_C") (pintype "passive"))
    )
    (net (code "73") (name "Net-(R35-Pad2)") (class "Default")
      (node (ref "R35") (pin "2") (pinfunction "2_2") (pintype "passive"))
      (node (ref "R36") (pin "1") (pinfunction "1_1") (pintype "passive"))
      (node (ref "T14") (pin "B") (pinfunction "B_B") (pintype "passive"))
    )
    (net (code "74") (name "Net-(R37-Pad2)") (class "Default")
      (node (ref "R37") (pin "2") (pinfunction "2_2") (pintype "passive"))
      (node (ref "R38") (pin "2") (pinfunction "2_2") (pintype "passive"))
      (node (ref "T15") (pin "B") (pinfunction "B_B") (pintype "passive"))
    )
    (net (code "75") (name "OK") (class "Default")
      (node (ref "IC6") (pin "2") (pinfunction "PC6_2") (pintype "bidirectional"))
      (node (ref "S2") (pin "2") (pinfunction "S_2") (pintype "passive"))
    )
    (net (code "76") (name "PWM") (class "Default")
      (node (ref "IC6") (pin "10") (pinfunction "PB0_10") (pintype "bidirectional"))
      (node (ref "Q2") (pin "1") (pinfunction "G_1") (pintype "passive"))
    )
    (net (code "77") (name "SWIM") (class "Default")
      (node (ref "IC6") (pin "3") (pinfunction "PA0_3") (pintype "bidirectional"))
      (node (ref "SV1") (pin "SWIM") (pinfunction "SWIM_SWIM") (pintype "bidirectional"))
    )
    (net (code "78") (name "UP") (class "Default")
      (node (ref "IC6") (pin "1") (pinfunction "PC5_1") (pintype "bidirectional"))
      (node (ref "S1") (pin "2") (pinfunction "S_2") (pintype "passive"))
    )
    (net (code "79") (name "VCC") (class "Default")
      (node (ref "C1") (pin "1") (pinfunction "1_1") (pintype "passive"))
      (node (ref "C2") (pin "1") (pinfunction "1_1") (pintype "passive"))
      (node (ref "C3") (pin "+") (pinfunction "+_+") (pintype "passive"))
      (node (ref "C4") (pin "1") (pinfunction "1_1") (pintype "passive"))
      (node (ref "C5") (pin "1") (pinfunction "1_1") (pintype "passive"))
      (node (ref "IC1") (pin "5") (pinfunction "VCC_5") (pintype "power_in"))
      (node (ref "IC2") (pin "10") (pinfunction "SCL_10") (pintype "input"))
      (node (ref "IC2") (pin "16") (pinfunction "VCC_16") (pintype "power_in"))
      (node (ref "IC7") (pin "1") (pinfunction "IN_1") (pintype "input"))
      (node (ref "IC7") (pin "3") (pinfunction "EN_3") (pintype "input"))
      (node (ref "J1") (pin "1") (pinfunction "1_1") (pintype "passive"))
      (node (ref "L1") (pin "1") (pinfunction "1_1") (pintype "passive"))
      (node (ref "SV1") (pin "VCC") (pinfunction "VCC_VCC") (pintype "power_in"))
    )
    (net (code "80") (name "unconnected-(IC2A-QH*-Pad9)") (class "Default")
      (node (ref "IC2") (pin "9") (pinfunction "QH*_9") (pintype "tri_state"))
    )
    (net (code "81") (name "unconnected-(IC6A-PB1-Pad11)") (class "Default")
      (node (ref "IC6") (pin "11") (pinfunction "PB1_11") (pintype "bidirectional"))
    )
    (net (code "82") (name "unconnected-(IC6A-PB2-Pad12)") (class "Default")
      (node (ref "IC6") (pin "12") (pinfunction "PB2_12") (pintype "bidirectional"))
    )
    (net (code "83") (name "unconnected-(IC6A-PB4-Pad14)") (class "Default")
      (node (ref "IC6") (pin "14") (pinfunction "PB4_14") (pintype "bidirectional"))
    )
    (net (code "84") (name "unconnected-(IC6A-PB5-Pad15)") (class "Default")
      (node (ref "IC6") (pin "15") (pinfunction "PB5_15") (pintype "bidirectional"))
    )
    (net (code "85") (name "unconnected-(IC6A-PB6-Pad16)") (class "Default")
      (node (ref "IC6") (pin "16") (pinfunction "PB6_16") (pintype "bidirectional"))
    )
    (net (code "86") (name "unconnected-(IC6A-PB7-Pad17)") (class "Default")
      (node (ref "IC6") (pin "17") (pinfunction "PB7_17") (pintype "bidirectional"))
    )
    (net (code "87") (name "unconnected-(IC6A-PC0-Pad18)") (class "Default")
      (node (ref "IC6") (pin "18") (pinfunction "PC0_18") (pintype "bidirectional"))
    )
    (net (code "88") (name "unconnected-(IC6A-PC1-Pad19)") (class "Default")
      (node (ref "IC6") (pin "19") (pinfunction "PC1_19") (pintype "bidirectional"))
    )
    (net (code "89") (name "unconnected-(IC6A-PC4-Pad20)") (class "Default")
      (node (ref "IC6") (pin "20") (pinfunction "PC4_20") (pintype "bidirectional"))
    )
    (net (code "90") (name "unconnected-(J1-Pad2)") (class "Default")
      (node (ref "J1") (pin "2") (pinfunction "2_2") (pintype "passive"))
    )
  )
)
